# Eagle_Template.net
KiCad netlist of a schematic drawn in EAGLE
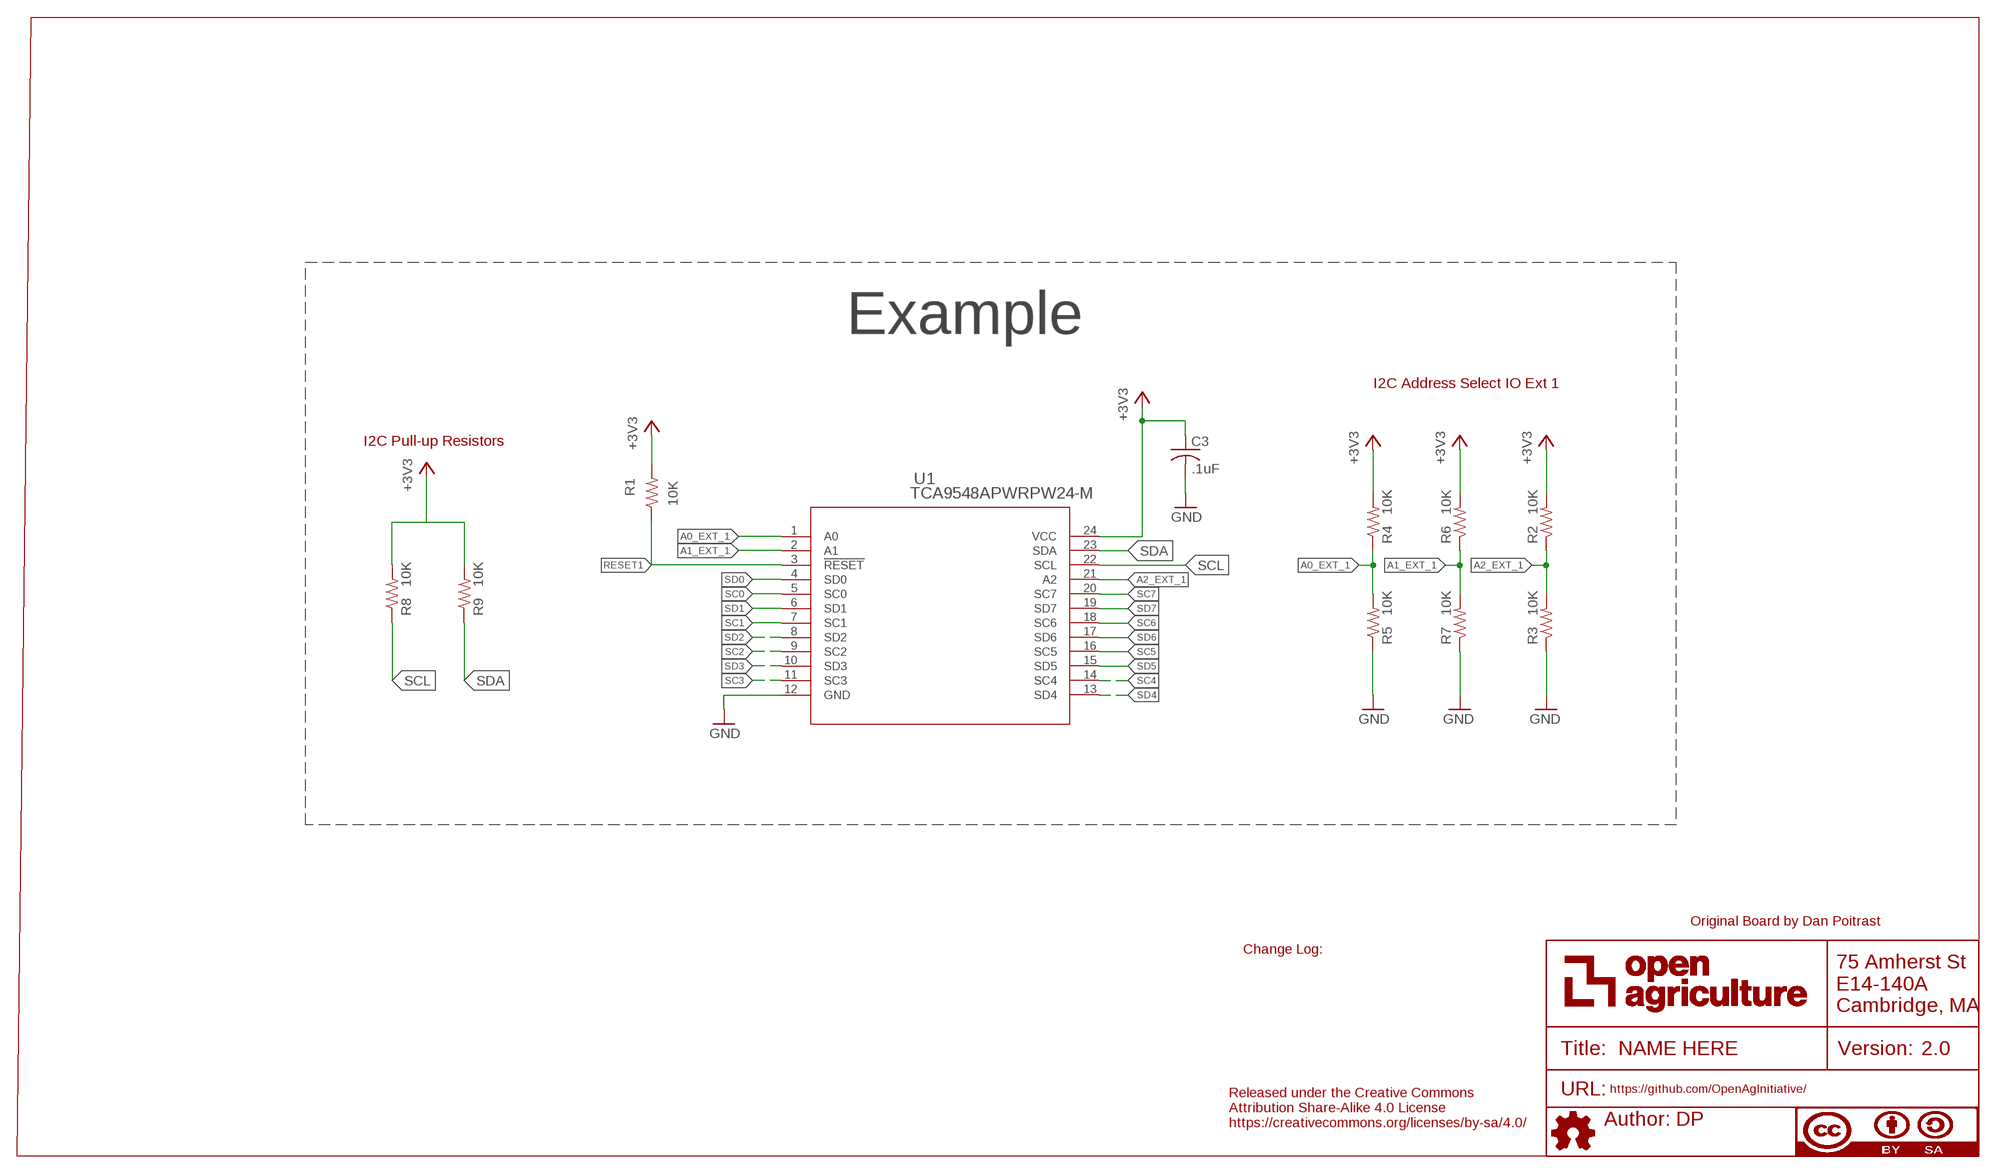
[diagram p0: schematic, sheet 1]

(export (version "E")
  (design (tool "Eeschema 10.0.6"))
  (components
    (comp (ref "ATTRIBUTES")
      (value "DOCFIELD")
      (footprint "eagle-import:DOCFIELD")
      (fields
        (field (name "AUTHOR") "DP")
        (field (name "TITLE") "NAME HERE")
        (field (name "URL") "https://github.com/OpenAgInitiative/")
        (field (name "VER") "2.0")
      )
      (libsource (lib "eagle-import") (part "DOCFIELD"))
    )
    (comp (ref "C3")
      (value ".1uF")
      (footprint "eagle-import:C0603@1")
      (libsource (lib "eagle-import") (part "C-USC0603"))
    )
    (comp (ref "R1")
      (value "10K")
      (footprint "eagle-import:R0603")
      (libsource (lib "eagle-import") (part "R-US_R0603"))
    )
    (comp (ref "R2")
      (value "10K")
      (footprint "eagle-import:0603-RES")
      (libsource (lib "eagle-import") (part "10KOHM-1/10W-1%(0603)0603"))
    )
    (comp (ref "R3")
      (value "10K")
      (footprint "eagle-import:0603-RES")
      (libsource (lib "eagle-import") (part "10KOHM-1/10W-1%(0603)0603"))
    )
    (comp (ref "R4")
      (value "10K")
      (footprint "eagle-import:0603-RES")
      (libsource (lib "eagle-import") (part "10KOHM-1/10W-1%(0603)0603"))
    )
    (comp (ref "R5")
      (value "10K")
      (footprint "eagle-import:0603-RES")
      (libsource (lib "eagle-import") (part "10KOHM-1/10W-1%(0603)0603"))
    )
    (comp (ref "R6")
      (value "10K")
      (footprint "eagle-import:0603-RES")
      (libsource (lib "eagle-import") (part "10KOHM-1/10W-1%(0603)0603"))
    )
    (comp (ref "R7")
      (value "10K")
      (footprint "eagle-import:0603-RES")
      (libsource (lib "eagle-import") (part "10KOHM-1/10W-1%(0603)0603"))
    )
    (comp (ref "R8")
      (value "10K")
      (footprint "eagle-import:0603-RES")
      (libsource (lib "eagle-import") (part "10KOHM-1/10W-1%(0603)0603"))
    )
    (comp (ref "R9")
      (value "10K")
      (footprint "eagle-import:0603-RES")
      (libsource (lib "eagle-import") (part "10KOHM-1/10W-1%(0603)0603"))
    )
    (comp (ref "U1")
      (value "TCA9548APWRPW24-M")
      (footprint "eagle-import:PW24-M")
      (fields (field (name "MANUFACTURER_PART_NUMBER") "TCA9548APWR"))
      (libsource (lib "eagle-import") (part "TCA9548APWRPW24-M"))
    )
  )
  (nets
    (net (code "1") (name "+3V3") (class "Default")
      (node (ref "C3") (pin "1") (pinfunction "1_1") (pintype "passive"))
      (node (ref "R1") (pin "2") (pinfunction "2_2") (pintype "passive"))
      (node (ref "R2") (pin "2") (pinfunction "2_2") (pintype "passive"))
      (node (ref "R4") (pin "2") (pinfunction "2_2") (pintype "passive"))
      (node (ref "R6") (pin "2") (pinfunction "2_2") (pintype "passive"))
      (node (ref "R8") (pin "2") (pinfunction "2_2") (pintype "passive"))
      (node (ref "R9") (pin "2") (pinfunction "2_2") (pintype "passive"))
      (node (ref "U1") (pin "24") (pinfunction "VCC_24") (pintype "power_in"))
    )
    (net (code "2") (name "A0_EXT_1") (class "Default")
      (node (ref "R4") (pin "1") (pinfunction "1_1") (pintype "passive"))
      (node (ref "R5") (pin "2") (pinfunction "2_2") (pintype "passive"))
      (node (ref "U1") (pin "1") (pinfunction "A0_1") (pintype "input"))
    )
    (net (code "3") (name "A1_EXT_1") (class "Default")
      (node (ref "R6") (pin "1") (pinfunction "1_1") (pintype "passive"))
      (node (ref "R7") (pin "2") (pinfunction "2_2") (pintype "passive"))
      (node (ref "U1") (pin "2") (pinfunction "A1_2") (pintype "input"))
    )
    (net (code "4") (name "A2_EXT_1") (class "Default")
      (node (ref "R2") (pin "1") (pinfunction "1_1") (pintype "passive"))
      (node (ref "R3") (pin "2") (pinfunction "2_2") (pintype "passive"))
      (node (ref "U1") (pin "21") (pinfunction "A2_21") (pintype "input"))
    )
    (net (code "5") (name "GND") (class "Default")
      (node (ref "C3") (pin "2") (pinfunction "2_2") (pintype "passive"))
      (node (ref "R3") (pin "1") (pinfunction "1_1") (pintype "passive"))
      (node (ref "R5") (pin "1") (pinfunction "1_1") (pintype "passive"))
      (node (ref "R7") (pin "1") (pinfunction "1_1") (pintype "passive"))
      (node (ref "U1") (pin "12") (pinfunction "GND_12") (pintype "power_in"))
    )
    (net (code "6") (name "RESET1") (class "Default")
      (node (ref "R1") (pin "1") (pinfunction "1_1") (pintype "passive"))
      (node (ref "U1") (pin "3") (pinfunction "~{RESET}_3") (pintype "input"))
    )
    (net (code "7") (name "SC0") (class "Default")
      (node (ref "U1") (pin "5") (pinfunction "SC0_5") (pintype "passive"))
    )
    (net (code "8") (name "SC1") (class "Default")
      (node (ref "U1") (pin "7") (pinfunction "SC1_7") (pintype "passive"))
    )
    (net (code "9") (name "SC2") (class "Default")
      (node (ref "U1") (pin "9") (pinfunction "SC2_9") (pintype "passive"))
    )
    (net (code "10") (name "SC3") (class "Default")
      (node (ref "U1") (pin "11") (pinfunction "SC3_11") (pintype "passive"))
    )
    (net (code "11") (name "SC4") (class "Default")
      (node (ref "U1") (pin "14") (pinfunction "SC4_14") (pintype "passive"))
    )
    (net (code "12") (name "SC5") (class "Default")
      (node (ref "U1") (pin "16") (pinfunction "SC5_16") (pintype "passive"))
    )
    (net (code "13") (name "SC6") (class "Default")
      (node (ref "U1") (pin "18") (pinfunction "SC6_18") (pintype "passive"))
    )
    (net (code "14") (name "SC7") (class "Default")
      (node (ref "U1") (pin "20") (pinfunction "SC7_20") (pintype "passive"))
    )
    (net (code "15") (name "SCL") (class "Default")
      (node (ref "R8") (pin "1") (pinfunction "1_1") (pintype "passive"))
      (node (ref "U1") (pin "22") (pinfunction "SCL_22") (pintype "passive"))
    )
    (net (code "16") (name "SD0") (class "Default")
      (node (ref "U1") (pin "4") (pinfunction "SD0_4") (pintype "passive"))
    )
    (net (code "17") (name "SD1") (class "Default")
      (node (ref "U1") (pin "6") (pinfunction "SD1_6") (pintype "passive"))
    )
    (net (code "18") (name "SD2") (class "Default")
      (node (ref "U1") (pin "8") (pinfunction "SD2_8") (pintype "passive"))
    )
    (net (code "19") (name "SD3") (class "Default")
      (node (ref "U1") (pin "10") (pinfunction "SD3_10") (pintype "passive"))
    )
    (net (code "20") (name "SD4") (class "Default")
      (node (ref "U1") (pin "13") (pinfunction "SD4_13") (pintype "passive"))
    )
    (net (code "21") (name "SD5") (class "Default")
      (node (ref "U1") (pin "15") (pinfunction "SD5_15") (pintype "passive"))
    )
    (net (code "22") (name "SD6") (class "Default")
      (node (ref "U1") (pin "17") (pinfunction "SD6_17") (pintype "passive"))
    )
    (net (code "23") (name "SD7") (class "Default")
      (node (ref "U1") (pin "19") (pinfunction "SD7_19") (pintype "passive"))
    )
    (net (code "24") (name "SDA") (class "Default")
      (node (ref "R9") (pin "1") (pinfunction "1_1") (pintype "passive"))
      (node (ref "U1") (pin "23") (pinfunction "SDA_23") (pintype "passive"))
    )
  )
)
